# Falling_safety_Sheet1.net
KiCad netlist of a schematic drawn in Altium Designer
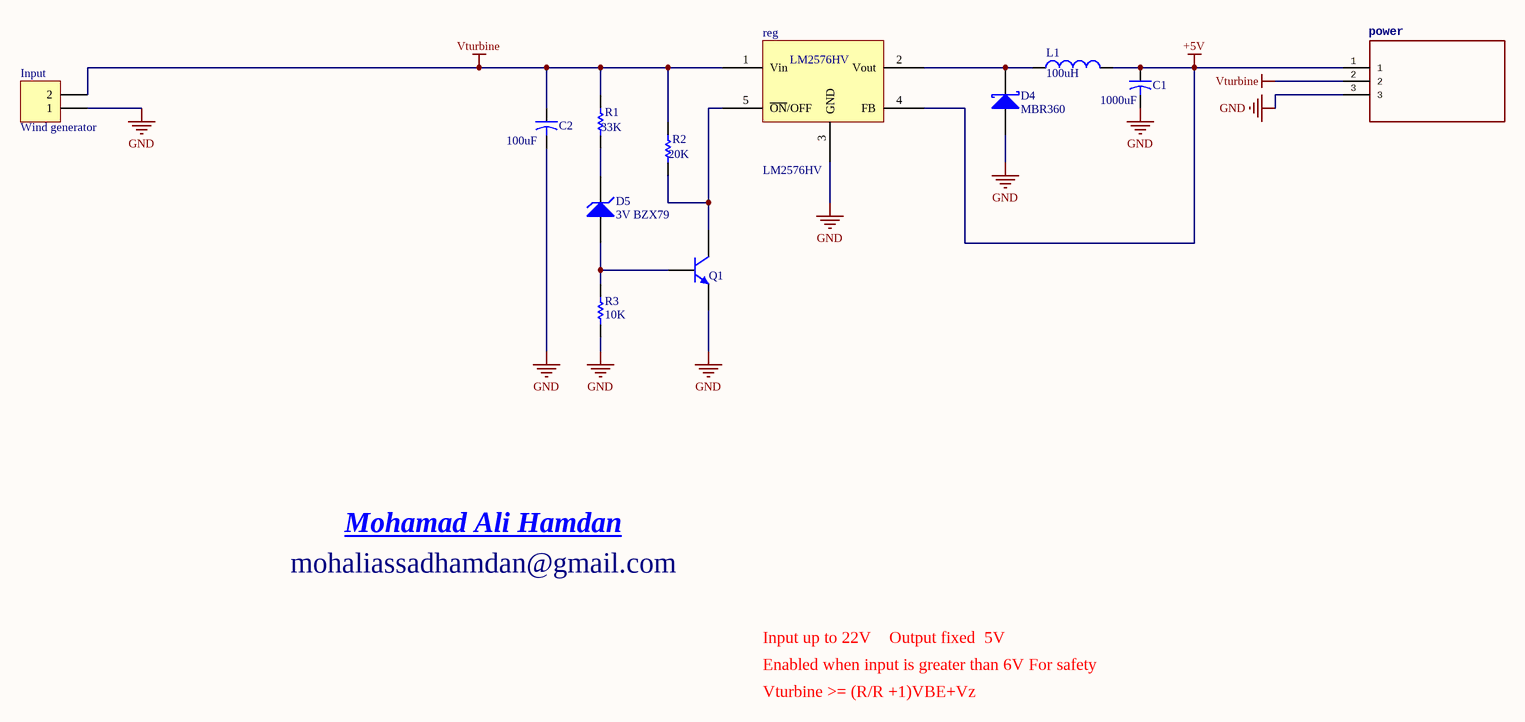
[diagram p0: Falling_safety_Sheet1.SchDoc]

(export (version "E")
  (design (tool "Eeschema 10.0.6"))
  (components
    (comp (ref "C1")
      (value "1000uF")
      (footprint "Capacitor_polarized_100uF")
      (description "Capacitor")
      (fields (field (name "Comment") "Cap2") (field (name "PUBLISHER") "Altium Limited"))
      (libsource (lib "Miscellaneous Devices") (part "Cap2"))
    )
    (comp (ref "C2")
      (value "100uF")
      (footprint "Capacitor_polarized_100uF")
      (description "Capacitor")
      (fields (field (name "Comment") "Cap2") (field (name "PUBLISHER") "Altium Limited"))
      (libsource (lib "Miscellaneous Devices") (part "Cap2"))
    )
    (comp (ref "D4")
      (value "MBR360")
      (footprint "diode 4007")
      (description "Schottky Rectifier")
      (fields (field (name "PUBLISHER") "Altium Limited"))
      (libsource (lib "Miscellaneous Devices") (part "Diode 10TQ035"))
    )
    (comp (ref "D5")
      (value "3V BZX79")
      (footprint "diode 4007")
      (description "Zener Diode")
      (fields (field (name "PUBLISHER") "Altium Limited"))
      (libsource (lib "Miscellaneous Devices") (part "D Zener"))
    )
    (comp (ref "Input")
      (value "Wind generator")
      (footprint "blue_connector_2pins")
      (description "Header, 2-Pin")
      (fields (field (name "PUBLISHER") "Altium Limited"))
      (libsource (lib "Miscellaneous Connectors") (part "Header 2"))
    )
    (comp (ref "L1")
      (value "100uH")
      (footprint "Coil_100uH")
      (description "Inductor")
      (fields (field (name "PUBLISHER") "Altium Limited"))
      (libsource (lib "Miscellaneous Devices") (part "Inductor"))
    )
    (comp (ref "power")
      (value "SAMTEC-HTSW-103-07-X-SJ")
      (footprint "SAMTEC-HTSW-103-07-X-S")
      (libsource (lib "SAMTEC-HTSW-103-07-X-S") (part "SAMTEC-HTSW-103-07-X-SJ"))
    )
    (comp (ref "Q1")
      (value "NPN")
      (footprint "TO-226-AA")
      (description "NPN Bipolar Transistor")
      (fields (field (name "PUBLISHER") "Altium Limited"))
      (libsource (lib "Miscellaneous Devices") (part "NPN"))
    )
    (comp (ref "R1")
      (value "33K")
      (footprint "resistor")
      (description "Resistor")
      (fields (field (name "Comment") "Res1") (field (name "PUBLISHER") "Altium Limited"))
      (libsource (lib "Miscellaneous Devices") (part "Res1"))
    )
    (comp (ref "R2")
      (value "20K")
      (footprint "resistor")
      (description "Resistor")
      (fields (field (name "Comment") "Res1") (field (name "PUBLISHER") "Altium Limited"))
      (libsource (lib "Miscellaneous Devices") (part "Res1"))
    )
    (comp (ref "R3")
      (value "10K")
      (footprint "resistor")
      (description "Resistor")
      (fields (field (name "Comment") "Res1") (field (name "PUBLISHER") "Altium Limited"))
      (libsource (lib "Miscellaneous Devices") (part "Res1"))
    )
    (comp (ref "reg")
      (value "LM2576HV")
      (footprint "LM2576HV")
      (description "3A Step-down Adjustable Output Switching Regulator with enable pin")
      (libsource (lib "LM2576HV") (part "LM2576HV"))
    )
  )
  (nets
    (net (code "1") (name "+5V") (class "Default")
      (node (ref "C1") (pin "1") (pinfunction "1_1") (pintype "passive"))
      (node (ref "L1") (pin "2") (pinfunction "2_2") (pintype "passive"))
      (node (ref "power") (pin "1") (pinfunction "1_1") (pintype "passive"))
      (node (ref "reg") (pin "4") (pinfunction "FB_4") (pintype "passive"))
    )
    (net (code "2") (name "GND") (class "Default")
      (node (ref "C1") (pin "2") (pinfunction "2_2") (pintype "passive"))
      (node (ref "C2") (pin "2") (pinfunction "2_2") (pintype "passive"))
      (node (ref "D4") (pin "3") (pinfunction "A_3") (pintype "passive"))
      (node (ref "Input") (pin "1") (pinfunction "1_1") (pintype "passive"))
      (node (ref "Q1") (pin "3") (pinfunction "E_3") (pintype "passive"))
      (node (ref "R3") (pin "1") (pinfunction "1_1") (pintype "passive"))
      (node (ref "power") (pin "3") (pinfunction "3_3") (pintype "passive"))
      (node (ref "reg") (pin "3") (pinfunction "GND_3") (pintype "passive"))
    )
    (net (code "3") (name "Net-(D4-K)") (class "Default")
      (node (ref "D4") (pin "1") (pinfunction "K_1") (pintype "passive"))
      (node (ref "L1") (pin "1") (pinfunction "1_1") (pintype "passive"))
      (node (ref "reg") (pin "2") (pinfunction "Vout_2") (pintype "passive"))
    )
    (net (code "4") (name "Net-(D5-A)") (class "Default")
      (node (ref "D5") (pin "1") (pinfunction "A_1") (pintype "passive"))
      (node (ref "Q1") (pin "2") (pinfunction "B_2") (pintype "passive"))
      (node (ref "R3") (pin "2") (pinfunction "2_2") (pintype "passive"))
    )
    (net (code "5") (name "Net-(D5-K)") (class "Default")
      (node (ref "D5") (pin "2") (pinfunction "K_2") (pintype "passive"))
      (node (ref "R1") (pin "1") (pinfunction "1_1") (pintype "passive"))
    )
    (net (code "6") (name "Net-(Q1-C)") (class "Default")
      (node (ref "Q1") (pin "1") (pinfunction "C_1") (pintype "passive"))
      (node (ref "R2") (pin "1") (pinfunction "1_1") (pintype "passive"))
      (node (ref "reg") (pin "5") (pinfunction "~{ON}/OFF_5") (pintype "passive"))
    )
    (net (code "7") (name "Vturbine") (class "Default")
      (node (ref "C2") (pin "1") (pinfunction "1_1") (pintype "passive"))
      (node (ref "Input") (pin "2") (pinfunction "2_2") (pintype "passive"))
      (node (ref "R1") (pin "2") (pinfunction "2_2") (pintype "passive"))
      (node (ref "R2") (pin "2") (pinfunction "2_2") (pintype "passive"))
      (node (ref "power") (pin "2") (pinfunction "2_2") (pintype "passive"))
      (node (ref "reg") (pin "1") (pinfunction "Vin_1") (pintype "passive"))
    )
  )
)
